# untitled_-_Kopia_mask.net
KiCad netlist of a schematic drawn in EAGLE
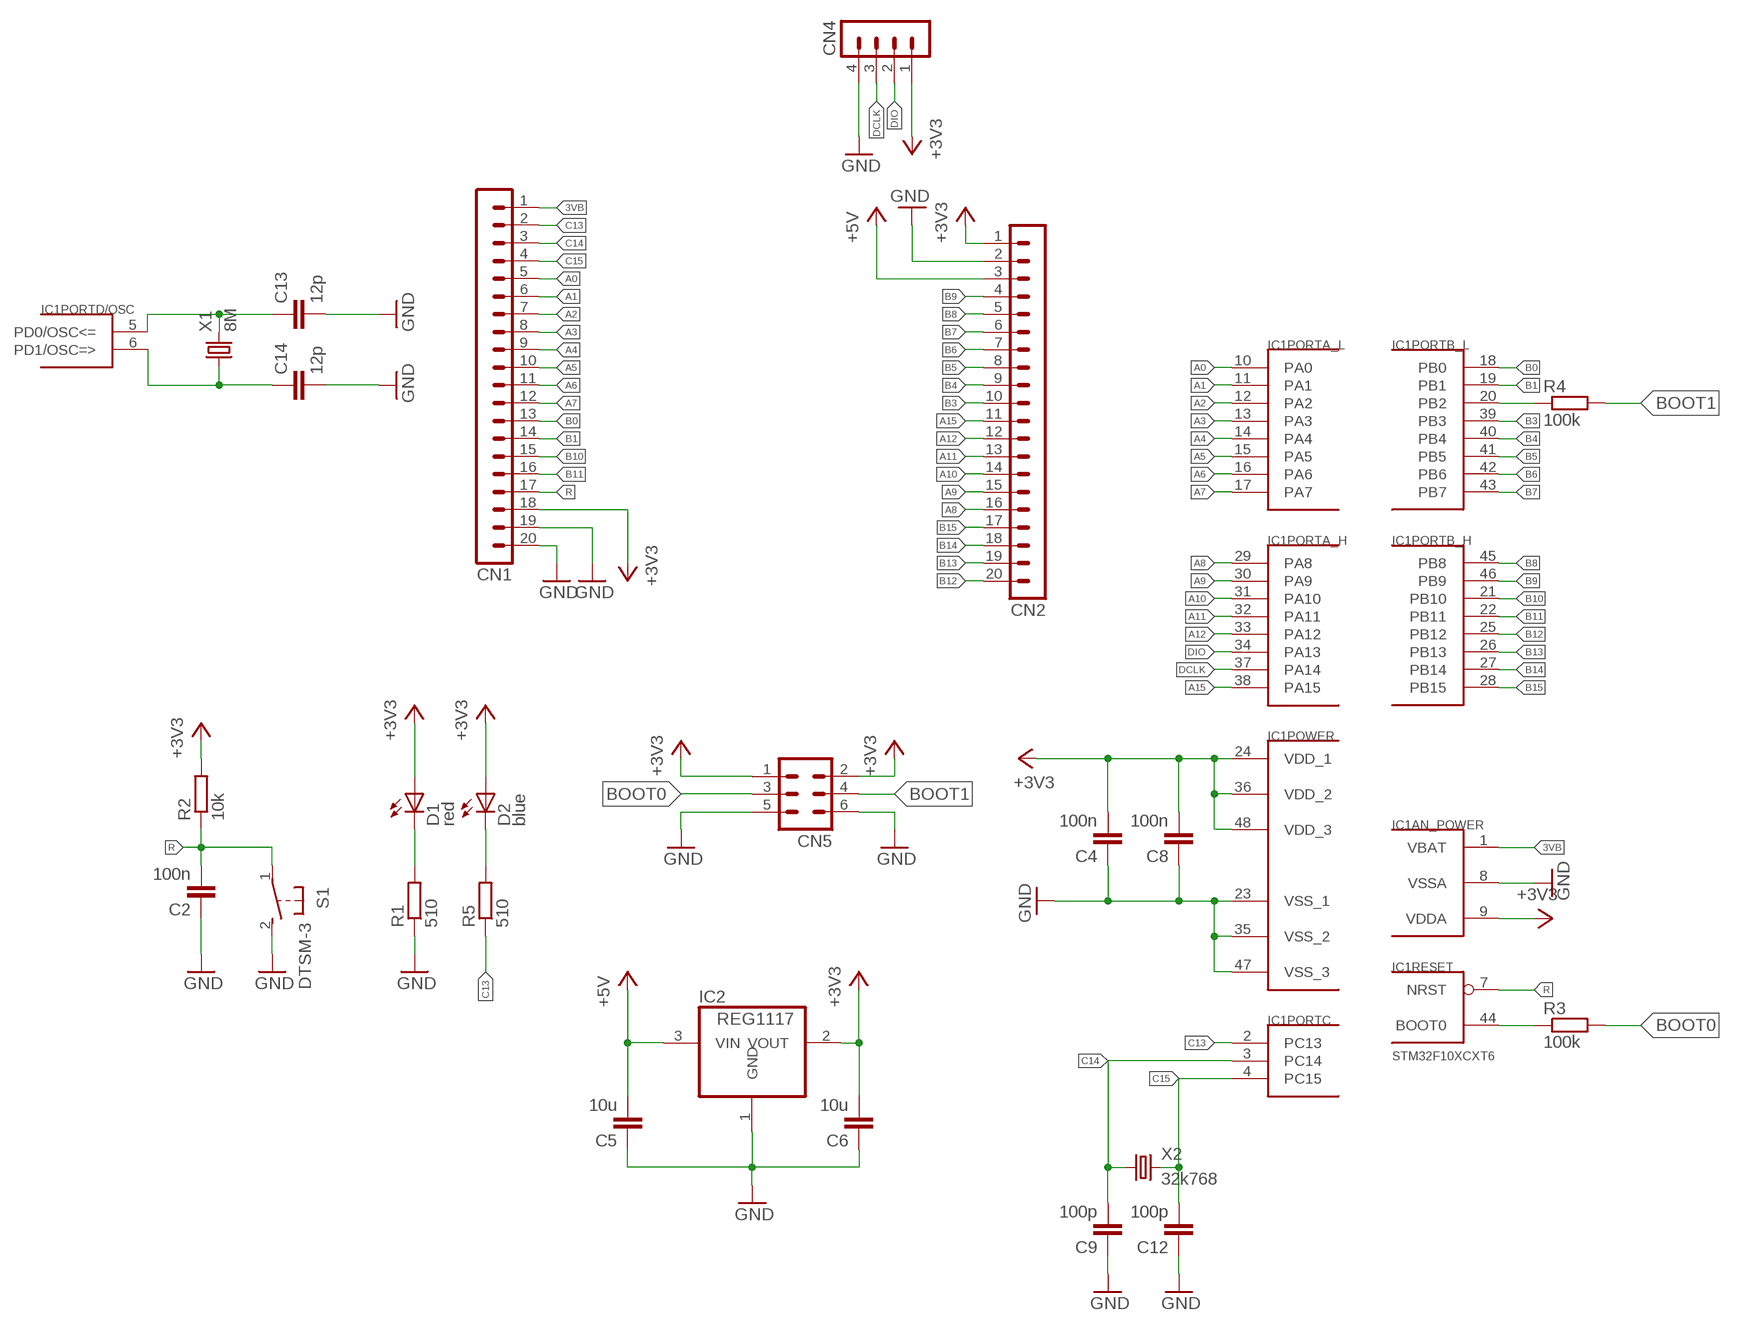
[diagram p0: schematic, sheet 1]

(export (version "E")
  (design (tool "Eeschema 10.0.6"))
  (components
    (comp (ref "C2")
      (value "100n")
      (footprint "eagle-import:C0805K")
      (libsource (lib "eagle-import") (part "C-EUC0805K"))
    )
    (comp (ref "C4")
      (value "100n")
      (footprint "eagle-import:C0805K")
      (libsource (lib "eagle-import") (part "C-EUC0805K"))
    )
    (comp (ref "C5")
      (value "10u")
      (footprint "eagle-import:C0805K")
      (libsource (lib "eagle-import") (part "C-EUC0805K"))
    )
    (comp (ref "C6")
      (value "10u")
      (footprint "eagle-import:C0805K")
      (libsource (lib "eagle-import") (part "C-EUC0805K"))
    )
    (comp (ref "C8")
      (value "100n")
      (footprint "eagle-import:C0805K")
      (libsource (lib "eagle-import") (part "C-EUC0805K"))
    )
    (comp (ref "C9")
      (value "100p")
      (footprint "eagle-import:C0805K")
      (libsource (lib "eagle-import") (part "C-EUC0805K"))
    )
    (comp (ref "C12")
      (value "100p")
      (footprint "eagle-import:C0805K")
      (libsource (lib "eagle-import") (part "C-EUC0805K"))
    )
    (comp (ref "C13")
      (value "12p")
      (footprint "eagle-import:C0805K")
      (libsource (lib "eagle-import") (part "C-EUC0805K"))
    )
    (comp (ref "C14")
      (value "12p")
      (footprint "eagle-import:C0805K")
      (libsource (lib "eagle-import") (part "C-EUC0805K"))
    )
    (comp (ref "CN1")
      (value "MA20-1L")
      (footprint "eagle-import:MA20-1L")
      (libsource (lib "eagle-import") (part "MA20-1L"))
    )
    (comp (ref "CN2")
      (value "MA20-1L")
      (footprint "eagle-import:MA20-1L")
      (libsource (lib "eagle-import") (part "MA20-1L"))
    )
    (comp (ref "CN4")
      (value "MA04-1")
      (footprint "eagle-import:MA04-1")
      (libsource (lib "eagle-import") (part "MA04-1"))
    )
    (comp (ref "CN5")
      (value "MA03-2")
      (footprint "eagle-import:MA03-2")
      (libsource (lib "eagle-import") (part "MA03-2"))
    )
    (comp (ref "D1")
      (value "red")
      (footprint "eagle-import:SML0805")
      (libsource (lib "eagle-import") (part "LEDSML0805"))
    )
    (comp (ref "D2")
      (value "blue")
      (footprint "eagle-import:SML0805")
      (libsource (lib "eagle-import") (part "LEDSML0805"))
    )
    (comp (ref "IC1")
      (value "STM32F10XCXT6")
      (footprint "eagle-import:TQFP48")
      (libsource (lib "eagle-import") (part "STM32F10XCXT6"))
    )
    (comp (ref "IC2")
      (value "REG1117")
      (footprint "eagle-import:SOT223")
      (libsource (lib "eagle-import") (part "REG1117"))
    )
    (comp (ref "R1")
      (value "510")
      (footprint "eagle-import:M0805")
      (libsource (lib "eagle-import") (part "R-EU_M0805"))
    )
    (comp (ref "R2")
      (value "10k")
      (footprint "eagle-import:R1206")
      (libsource (lib "eagle-import") (part "R-EU_R1206"))
    )
    (comp (ref "R3")
      (value "100k")
      (footprint "eagle-import:M0805")
      (libsource (lib "eagle-import") (part "R-EU_M0805"))
    )
    (comp (ref "R4")
      (value "100k")
      (footprint "eagle-import:M0805")
      (libsource (lib "eagle-import") (part "R-EU_M0805"))
    )
    (comp (ref "R5")
      (value "510")
      (footprint "eagle-import:M0805")
      (libsource (lib "eagle-import") (part "R-EU_M0805"))
    )
    (comp (ref "S1")
      (value "DTSM-3")
      (footprint "eagle-import:DTSM-3")
      (libsource (lib "eagle-import") (part "DTSM-3"))
    )
    (comp (ref "X1")
      (value "8M")
      (footprint "eagle-import:HC49_S")
      (libsource (lib "eagle-import") (part "CRYSTALHC49S"))
    )
    (comp (ref "X2")
      (value "32k768")
      (footprint "eagle-import:TC26H")
      (libsource (lib "eagle-import") (part "CRYSTALTC26H"))
    )
  )
  (nets
    (net (code "1") (name "+3V3") (class "Default")
      (node (ref "C4") (pin "2") (pinfunction "2_2") (pintype "passive"))
      (node (ref "C6") (pin "2") (pinfunction "2_2") (pintype "passive"))
      (node (ref "C8") (pin "2") (pinfunction "2_2") (pintype "passive"))
      (node (ref "CN1") (pin "18") (pinfunction "18_18") (pintype "passive"))
      (node (ref "CN2") (pin "1") (pinfunction "1_1") (pintype "passive"))
      (node (ref "CN4") (pin "1") (pinfunction "1_1") (pintype "passive"))
      (node (ref "CN5") (pin "1") (pinfunction "1_1") (pintype "passive"))
      (node (ref "CN5") (pin "2") (pinfunction "2_2") (pintype "passive"))
      (node (ref "D1") (pin "A") (pinfunction "A_A") (pintype "passive"))
      (node (ref "D2") (pin "A") (pinfunction "A_A") (pintype "passive"))
      (node (ref "IC1") (pin "24") (pinfunction "VDD_1_24") (pintype "power_in"))
      (node (ref "IC1") (pin "36") (pinfunction "VDD_2_36") (pintype "power_in"))
      (node (ref "IC1") (pin "48") (pinfunction "VDD_3_48") (pintype "power_in"))
      (node (ref "IC1") (pin "9") (pinfunction "VDDA_9") (pintype "power_in"))
      (node (ref "IC2") (pin "2") (pinfunction "VOUT_2") (pintype "output"))
      (node (ref "R2") (pin "2") (pinfunction "2_2") (pintype "passive"))
    )
    (net (code "2") (name "+5V") (class "Default")
      (node (ref "C5") (pin "2") (pinfunction "2_2") (pintype "passive"))
      (node (ref "CN2") (pin "3") (pinfunction "3_3") (pintype "passive"))
      (node (ref "IC2") (pin "3") (pinfunction "VIN_3") (pintype "input"))
    )
    (net (code "3") (name "3VB") (class "Default")
      (node (ref "CN1") (pin "1") (pinfunction "1_1") (pintype "passive"))
      (node (ref "IC1") (pin "1") (pinfunction "VBAT_1") (pintype "power_in"))
    )
    (net (code "4") (name "A0") (class "Default")
      (node (ref "CN1") (pin "5") (pinfunction "5_5") (pintype "passive"))
      (node (ref "IC1") (pin "10") (pinfunction "PA0_10") (pintype "bidirectional"))
    )
    (net (code "5") (name "A1") (class "Default")
      (node (ref "CN1") (pin "6") (pinfunction "6_6") (pintype "passive"))
      (node (ref "IC1") (pin "11") (pinfunction "PA1_11") (pintype "bidirectional"))
    )
    (net (code "6") (name "A2") (class "Default")
      (node (ref "CN1") (pin "7") (pinfunction "7_7") (pintype "passive"))
      (node (ref "IC1") (pin "12") (pinfunction "PA2_12") (pintype "bidirectional"))
    )
    (net (code "7") (name "A3") (class "Default")
      (node (ref "CN1") (pin "8") (pinfunction "8_8") (pintype "passive"))
      (node (ref "IC1") (pin "13") (pinfunction "PA3_13") (pintype "bidirectional"))
    )
    (net (code "8") (name "A4") (class "Default")
      (node (ref "CN1") (pin "9") (pinfunction "9_9") (pintype "passive"))
      (node (ref "IC1") (pin "14") (pinfunction "PA4_14") (pintype "bidirectional"))
    )
    (net (code "9") (name "A5") (class "Default")
      (node (ref "CN1") (pin "10") (pinfunction "10_10") (pintype "passive"))
      (node (ref "IC1") (pin "15") (pinfunction "PA5_15") (pintype "bidirectional"))
    )
    (net (code "10") (name "A6") (class "Default")
      (node (ref "CN1") (pin "11") (pinfunction "11_11") (pintype "passive"))
      (node (ref "IC1") (pin "16") (pinfunction "PA6_16") (pintype "bidirectional"))
    )
    (net (code "11") (name "A7") (class "Default")
      (node (ref "CN1") (pin "12") (pinfunction "12_12") (pintype "passive"))
      (node (ref "IC1") (pin "17") (pinfunction "PA7_17") (pintype "bidirectional"))
    )
    (net (code "12") (name "A8") (class "Default")
      (node (ref "CN2") (pin "16") (pinfunction "16_16") (pintype "passive"))
      (node (ref "IC1") (pin "29") (pinfunction "PA8_29") (pintype "bidirectional"))
    )
    (net (code "13") (name "A9") (class "Default")
      (node (ref "CN2") (pin "15") (pinfunction "15_15") (pintype "passive"))
      (node (ref "IC1") (pin "30") (pinfunction "PA9_30") (pintype "bidirectional"))
    )
    (net (code "14") (name "A10") (class "Default")
      (node (ref "CN2") (pin "14") (pinfunction "14_14") (pintype "passive"))
      (node (ref "IC1") (pin "31") (pinfunction "PA10_31") (pintype "bidirectional"))
    )
    (net (code "15") (name "A11") (class "Default")
      (node (ref "CN2") (pin "13") (pinfunction "13_13") (pintype "passive"))
      (node (ref "IC1") (pin "32") (pinfunction "PA11_32") (pintype "bidirectional"))
    )
    (net (code "16") (name "A12") (class "Default")
      (node (ref "CN2") (pin "12") (pinfunction "12_12") (pintype "passive"))
      (node (ref "IC1") (pin "33") (pinfunction "PA12_33") (pintype "bidirectional"))
    )
    (net (code "17") (name "A15") (class "Default")
      (node (ref "CN2") (pin "11") (pinfunction "11_11") (pintype "passive"))
      (node (ref "IC1") (pin "38") (pinfunction "PA15_38") (pintype "bidirectional"))
    )
    (net (code "18") (name "B0") (class "Default")
      (node (ref "CN1") (pin "13") (pinfunction "13_13") (pintype "passive"))
      (node (ref "IC1") (pin "18") (pinfunction "PB0_18") (pintype "bidirectional"))
    )
    (net (code "19") (name "B1") (class "Default")
      (node (ref "CN1") (pin "14") (pinfunction "14_14") (pintype "passive"))
      (node (ref "IC1") (pin "19") (pinfunction "PB1_19") (pintype "bidirectional"))
    )
    (net (code "20") (name "B3") (class "Default")
      (node (ref "CN2") (pin "10") (pinfunction "10_10") (pintype "passive"))
      (node (ref "IC1") (pin "39") (pinfunction "PB3_39") (pintype "bidirectional"))
    )
    (net (code "21") (name "B4") (class "Default")
      (node (ref "CN2") (pin "9") (pinfunction "9_9") (pintype "passive"))
      (node (ref "IC1") (pin "40") (pinfunction "PB4_40") (pintype "bidirectional"))
    )
    (net (code "22") (name "B5") (class "Default")
      (node (ref "CN2") (pin "8") (pinfunction "8_8") (pintype "passive"))
      (node (ref "IC1") (pin "41") (pinfunction "PB5_41") (pintype "bidirectional"))
    )
    (net (code "23") (name "B6") (class "Default")
      (node (ref "CN2") (pin "7") (pinfunction "7_7") (pintype "passive"))
      (node (ref "IC1") (pin "42") (pinfunction "PB6_42") (pintype "bidirectional"))
    )
    (net (code "24") (name "B7") (class "Default")
      (node (ref "CN2") (pin "6") (pinfunction "6_6") (pintype "passive"))
      (node (ref "IC1") (pin "43") (pinfunction "PB7_43") (pintype "bidirectional"))
    )
    (net (code "25") (name "B8") (class "Default")
      (node (ref "CN2") (pin "5") (pinfunction "5_5") (pintype "passive"))
      (node (ref "IC1") (pin "45") (pinfunction "PB8_45") (pintype "bidirectional"))
    )
    (net (code "26") (name "B9") (class "Default")
      (node (ref "CN2") (pin "4") (pinfunction "4_4") (pintype "passive"))
      (node (ref "IC1") (pin "46") (pinfunction "PB9_46") (pintype "bidirectional"))
    )
    (net (code "27") (name "B10") (class "Default")
      (node (ref "CN1") (pin "15") (pinfunction "15_15") (pintype "passive"))
      (node (ref "IC1") (pin "21") (pinfunction "PB10_21") (pintype "bidirectional"))
    )
    (net (code "28") (name "B11") (class "Default")
      (node (ref "CN1") (pin "16") (pinfunction "16_16") (pintype "passive"))
      (node (ref "IC1") (pin "22") (pinfunction "PB11_22") (pintype "bidirectional"))
    )
    (net (code "29") (name "B12") (class "Default")
      (node (ref "CN2") (pin "20") (pinfunction "20_20") (pintype "passive"))
      (node (ref "IC1") (pin "25") (pinfunction "PB12_25") (pintype "bidirectional"))
    )
    (net (code "30") (name "B13") (class "Default")
      (node (ref "CN2") (pin "19") (pinfunction "19_19") (pintype "passive"))
      (node (ref "IC1") (pin "26") (pinfunction "PB13_26") (pintype "bidirectional"))
    )
    (net (code "31") (name "B14") (class "Default")
      (node (ref "CN2") (pin "18") (pinfunction "18_18") (pintype "passive"))
      (node (ref "IC1") (pin "27") (pinfunction "PB14_27") (pintype "bidirectional"))
    )
    (net (code "32") (name "B15") (class "Default")
      (node (ref "CN2") (pin "17") (pinfunction "17_17") (pintype "passive"))
      (node (ref "IC1") (pin "28") (pinfunction "PB15_28") (pintype "bidirectional"))
    )
    (net (code "33") (name "BOOT0") (class "Default")
      (node (ref "CN5") (pin "3") (pinfunction "3_3") (pintype "passive"))
      (node (ref "R3") (pin "2") (pinfunction "2_2") (pintype "passive"))
    )
    (net (code "34") (name "BOOT1") (class "Default")
      (node (ref "CN5") (pin "4") (pinfunction "4_4") (pintype "passive"))
      (node (ref "R4") (pin "2") (pinfunction "2_2") (pintype "passive"))
    )
    (net (code "35") (name "C13") (class "Default")
      (node (ref "CN1") (pin "2") (pinfunction "2_2") (pintype "passive"))
      (node (ref "IC1") (pin "2") (pinfunction "PC13_2") (pintype "bidirectional"))
      (node (ref "R5") (pin "1") (pinfunction "1_1") (pintype "passive"))
    )
    (net (code "36") (name "C14") (class "Default")
      (node (ref "C9") (pin "2") (pinfunction "2_2") (pintype "passive"))
      (node (ref "CN1") (pin "3") (pinfunction "3_3") (pintype "passive"))
      (node (ref "IC1") (pin "3") (pinfunction "PC14_3") (pintype "bidirectional"))
      (node (ref "X2") (pin "1") (pinfunction "1_1") (pintype "passive"))
    )
    (net (code "37") (name "C15") (class "Default")
      (node (ref "C12") (pin "2") (pinfunction "2_2") (pintype "passive"))
      (node (ref "CN1") (pin "4") (pinfunction "4_4") (pintype "passive"))
      (node (ref "IC1") (pin "4") (pinfunction "PC15_4") (pintype "bidirectional"))
      (node (ref "X2") (pin "2") (pinfunction "2_2") (pintype "passive"))
    )
    (net (code "38") (name "DCLK") (class "Default")
      (node (ref "CN4") (pin "3") (pinfunction "3_3") (pintype "passive"))
      (node (ref "IC1") (pin "37") (pinfunction "PA14_37") (pintype "bidirectional"))
    )
    (net (code "39") (name "DIO") (class "Default")
      (node (ref "CN4") (pin "2") (pinfunction "2_2") (pintype "passive"))
      (node (ref "IC1") (pin "34") (pinfunction "PA13_34") (pintype "bidirectional"))
    )
    (net (code "40") (name "GND") (class "Default")
      (node (ref "C12") (pin "1") (pinfunction "1_1") (pintype "passive"))
      (node (ref "C13") (pin "2") (pinfunction "2_2") (pintype "passive"))
      (node (ref "C14") (pin "2") (pinfunction "2_2") (pintype "passive"))
      (node (ref "C2") (pin "1") (pinfunction "1_1") (pintype "passive"))
      (node (ref "C4") (pin "1") (pinfunction "1_1") (pintype "passive"))
      (node (ref "C5") (pin "1") (pinfunction "1_1") (pintype "passive"))
      (node (ref "C6") (pin "1") (pinfunction "1_1") (pintype "passive"))
      (node (ref "C8") (pin "1") (pinfunction "1_1") (pintype "passive"))
      (node (ref "C9") (pin "1") (pinfunction "1_1") (pintype "passive"))
      (node (ref "CN1") (pin "19") (pinfunction "19_19") (pintype "passive"))
      (node (ref "CN1") (pin "20") (pinfunction "20_20") (pintype "passive"))
      (node (ref "CN2") (pin "2") (pinfunction "2_2") (pintype "passive"))
      (node (ref "CN4") (pin "4") (pinfunction "4_4") (pintype "passive"))
      (node (ref "CN5") (pin "5") (pinfunction "5_5") (pintype "passive"))
      (node (ref "CN5") (pin "6") (pinfunction "6_6") (pintype "passive"))
      (node (ref "IC1") (pin "23") (pinfunction "VSS_1_23") (pintype "power_in"))
      (node (ref "IC1") (pin "35") (pinfunction "VSS_2_35") (pintype "power_in"))
      (node (ref "IC1") (pin "47") (pinfunction "VSS_3_47") (pintype "power_in"))
      (node (ref "IC1") (pin "8") (pinfunction "VSSA_8") (pintype "power_in"))
      (node (ref "IC2") (pin "1") (pinfunction "GND_1") (pintype "power_in"))
      (node (ref "R1") (pin "1") (pinfunction "1_1") (pintype "passive"))
      (node (ref "S1") (pin "2") (pinfunction "2_2") (pintype "passive"))
    )
    (net (code "41") (name "Net-(D1-PadC)") (class "Default")
      (node (ref "D1") (pin "C") (pinfunction "C_C") (pintype "passive"))
      (node (ref "R1") (pin "2") (pinfunction "2_2") (pintype "passive"))
    )
    (net (code "42") (name "Net-(D2-PadC)") (class "Default")
      (node (ref "D2") (pin "C") (pinfunction "C_C") (pintype "passive"))
      (node (ref "R5") (pin "2") (pinfunction "2_2") (pintype "passive"))
    )
    (net (code "43") (name "Net-(IC1E-PB2)") (class "Default")
      (node (ref "IC1") (pin "20") (pinfunction "PB2_20") (pintype "bidirectional"))
      (node (ref "R4") (pin "1") (pinfunction "1_1") (pintype "passive"))
    )
    (net (code "44") (name "Net-(IC1G-PD0{slash}OSC<=)") (class "Default")
      (node (ref "C13") (pin "1") (pinfunction "1_1") (pintype "passive"))
      (node (ref "IC1") (pin "5") (pinfunction "PD0/OSC<=_5") (pintype "bidirectional"))
      (node (ref "X1") (pin "2") (pinfunction "2_2") (pintype "passive"))
    )
    (net (code "45") (name "Net-(IC1G-PD1{slash}OSC=>)") (class "Default")
      (node (ref "C14") (pin "1") (pinfunction "1_1") (pintype "passive"))
      (node (ref "IC1") (pin "6") (pinfunction "PD1/OSC=>_6") (pintype "bidirectional"))
      (node (ref "X1") (pin "1") (pinfunction "1_1") (pintype "passive"))
    )
    (net (code "46") (name "Net-(IC1I-BOOT0)") (class "Default")
      (node (ref "IC1") (pin "44") (pinfunction "BOOT0_44") (pintype "input"))
      (node (ref "R3") (pin "1") (pinfunction "1_1") (pintype "passive"))
    )
    (net (code "47") (name "R") (class "Default")
      (node (ref "C2") (pin "2") (pinfunction "2_2") (pintype "passive"))
      (node (ref "CN1") (pin "17") (pinfunction "17_17") (pintype "passive"))
      (node (ref "IC1") (pin "7") (pinfunction "NRST_7") (pintype "input"))
      (node (ref "R2") (pin "1") (pinfunction "1_1") (pintype "passive"))
      (node (ref "S1") (pin "1") (pinfunction "1_1") (pintype "passive"))
    )
  )
)
